# p128a.net
KiCad netlist of a schematic drawn in EAGLE
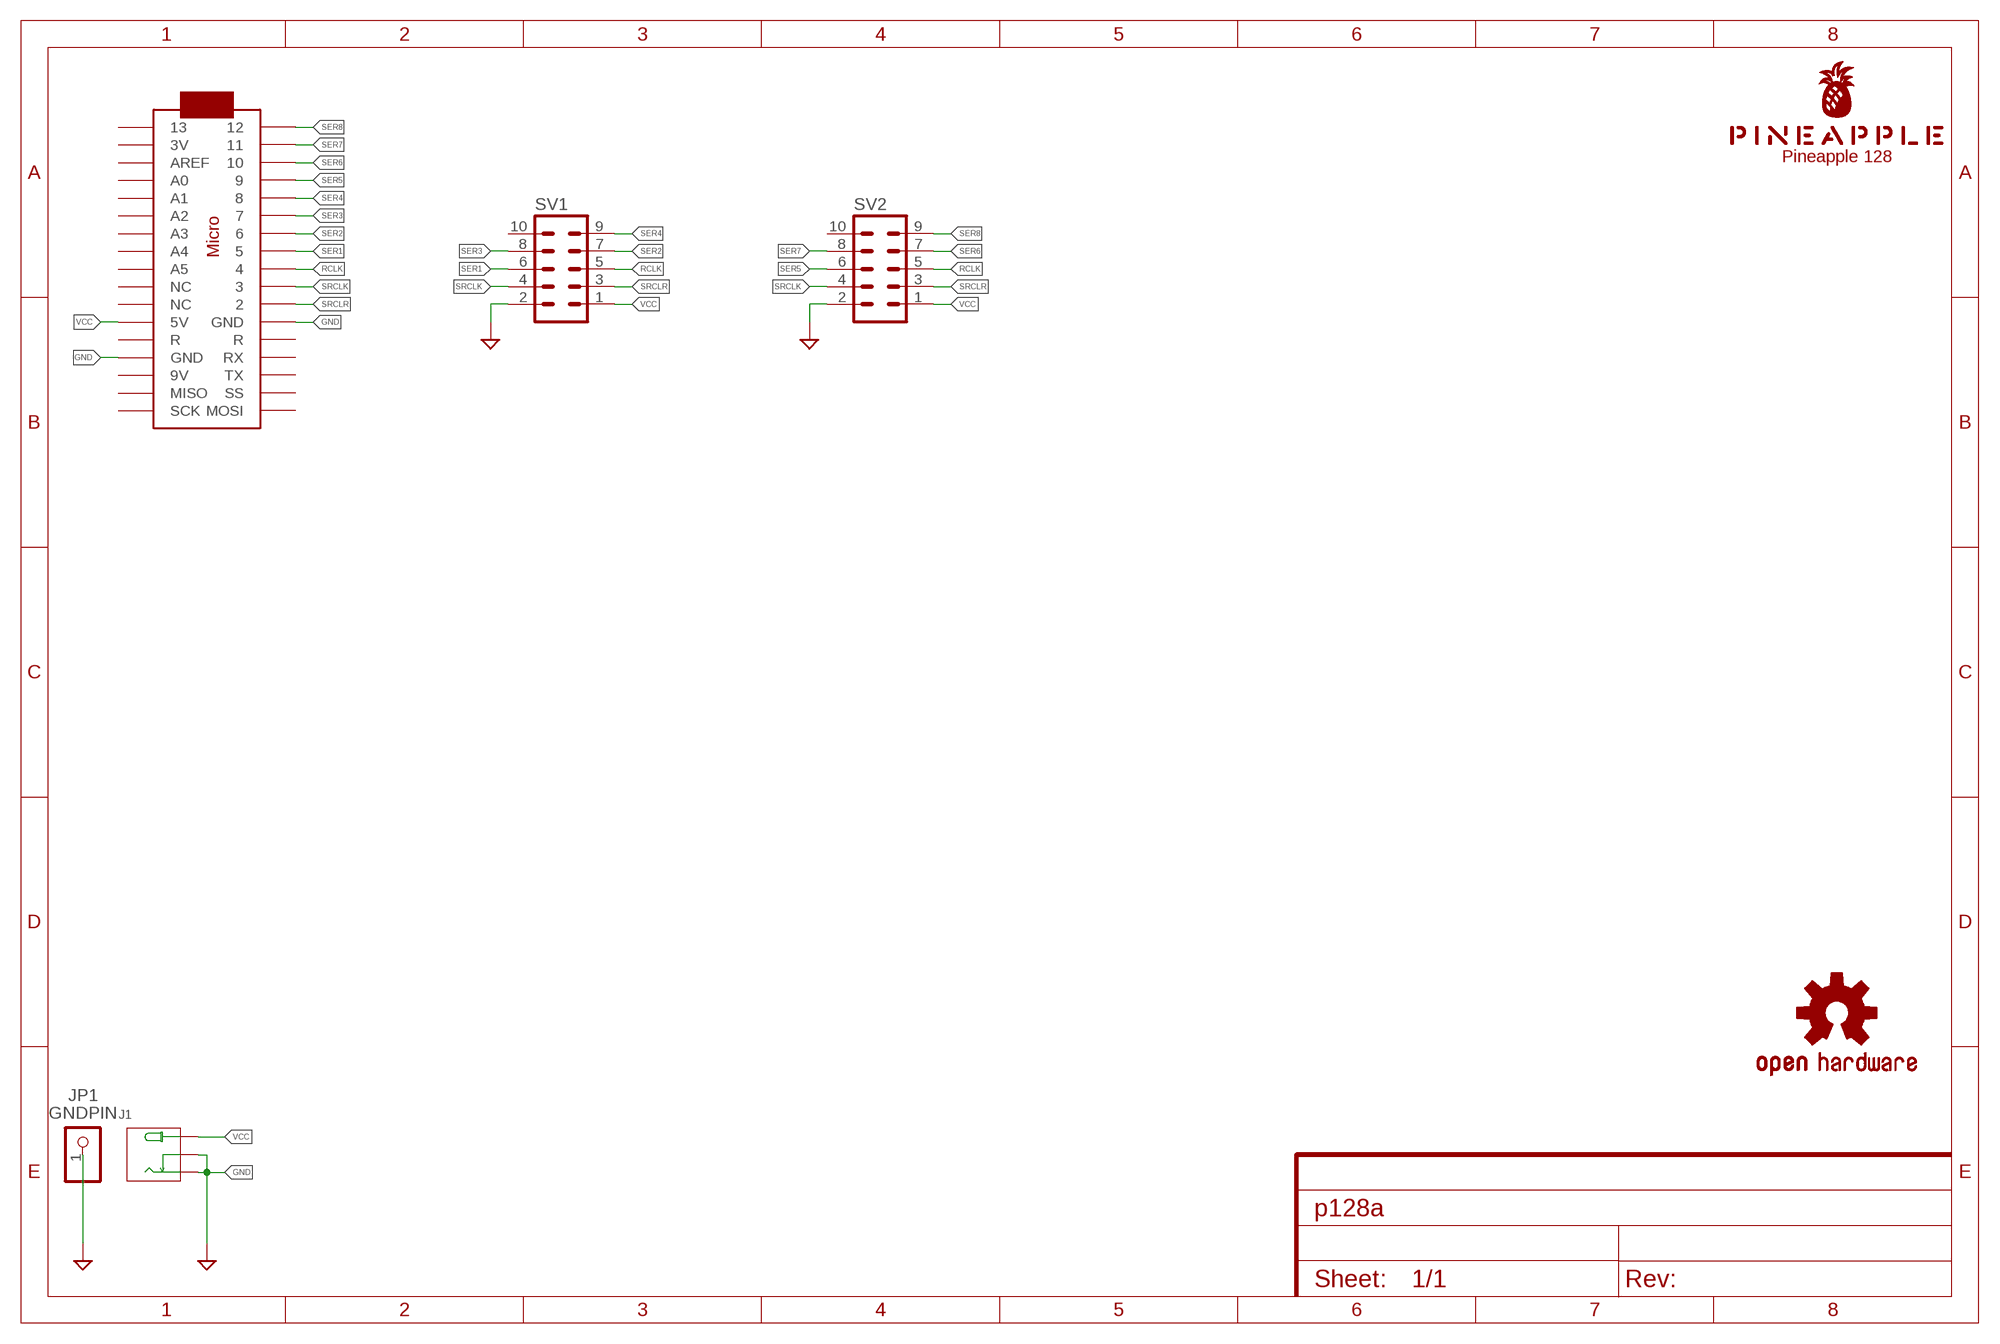
[diagram p0: schematic, sheet 1]

(export (version "E")
  (design (tool "Eeschema 10.0.6"))
  (components
    (comp (ref "J1")
      (value "JACK-DC-005'DC-005'")
      (footprint "eagle-import:3P-L14.2_W11.0_H9.0MM")
      (libsource (lib "eagle-import") (part "JACK-DC-005'DC-005'"))
    )
    (comp (ref "JP1")
      (value "GNDPIN")
      (footprint "eagle-import:1X01")
      (libsource (lib "eagle-import") (part "PINHD-1X1"))
    )
    (comp (ref "LOGO1")
      (value "OSHW-LOGOS-COPPER")
      (footprint "eagle-import:OSHW-LOGO-S_COPPER")
      (libsource (lib "eagle-import") (part "OSHW-LOGOS-COPPER"))
    )
    (comp (ref "MC1")
      (value "ARDUINOMICRO")
      (footprint "eagle-import:ARDUINOMICRO")
      (libsource (lib "eagle-import") (part "ARDUINOMICRO"))
    )
    (comp (ref "SV1")
      (value "ML10L")
      (footprint "eagle-import:ML10L")
      (libsource (lib "eagle-import") (part "ML10L"))
    )
    (comp (ref "SV2")
      (value "ML10L")
      (footprint "eagle-import:ML10L")
      (libsource (lib "eagle-import") (part "ML10L"))
    )
    (comp (ref "U$1")
      (value "PINEAPPLE450_SILK")
      (footprint "eagle-import:PINEAPPLE450_SILK")
      (libsource (lib "eagle-import") (part "PINEAPPLE450_SILK"))
    )
  )
  (nets
    (net (code "1") (name "GND") (class "Default")
      (node (ref "J1") (pin "-1") (pinfunction "-_-1") (pintype "bidirectional"))
      (node (ref "J1") (pin "-2") (pinfunction "CDN_-2") (pintype "bidirectional"))
      (node (ref "JP1") (pin "1") (pinfunction "1_1") (pintype "passive"))
      (node (ref "MC1") (pin "P$12") (pinfunction "GND_P$12") (pintype "bidirectional"))
      (node (ref "MC1") (pin "P$21") (pinfunction "GND_P$21") (pintype "bidirectional"))
      (node (ref "SV1") (pin "2") (pinfunction "2_2") (pintype "passive"))
      (node (ref "SV2") (pin "2") (pinfunction "2_2") (pintype "passive"))
    )
    (net (code "2") (name "RCLK") (class "Default")
      (node (ref "MC1") (pin "P$9") (pinfunction "4_P$9") (pintype "bidirectional"))
      (node (ref "SV1") (pin "5") (pinfunction "5_5") (pintype "passive"))
      (node (ref "SV2") (pin "5") (pinfunction "5_5") (pintype "passive"))
    )
    (net (code "3") (name "SER1") (class "Default")
      (node (ref "MC1") (pin "P$8") (pinfunction "5_P$8") (pintype "bidirectional"))
      (node (ref "SV1") (pin "6") (pinfunction "6_6") (pintype "passive"))
    )
    (net (code "4") (name "SER2") (class "Default")
      (node (ref "MC1") (pin "P$7") (pinfunction "6_P$7") (pintype "bidirectional"))
      (node (ref "SV1") (pin "7") (pinfunction "7_7") (pintype "passive"))
    )
    (net (code "5") (name "SER3") (class "Default")
      (node (ref "MC1") (pin "P$6") (pinfunction "7_P$6") (pintype "bidirectional"))
      (node (ref "SV1") (pin "8") (pinfunction "8_8") (pintype "passive"))
    )
    (net (code "6") (name "SER4") (class "Default")
      (node (ref "MC1") (pin "P$5") (pinfunction "8_P$5") (pintype "bidirectional"))
      (node (ref "SV1") (pin "9") (pinfunction "9_9") (pintype "passive"))
    )
    (net (code "7") (name "SER5") (class "Default")
      (node (ref "MC1") (pin "P$4") (pinfunction "9_P$4") (pintype "bidirectional"))
      (node (ref "SV2") (pin "6") (pinfunction "6_6") (pintype "passive"))
    )
    (net (code "8") (name "SER6") (class "Default")
      (node (ref "MC1") (pin "P$3") (pinfunction "10_P$3") (pintype "bidirectional"))
      (node (ref "SV2") (pin "7") (pinfunction "7_7") (pintype "passive"))
    )
    (net (code "9") (name "SER7") (class "Default")
      (node (ref "MC1") (pin "P$2") (pinfunction "11_P$2") (pintype "bidirectional"))
      (node (ref "SV2") (pin "8") (pinfunction "8_8") (pintype "passive"))
    )
    (net (code "10") (name "SER8") (class "Default")
      (node (ref "MC1") (pin "P$1") (pinfunction "12_P$1") (pintype "bidirectional"))
      (node (ref "SV2") (pin "9") (pinfunction "9_9") (pintype "passive"))
    )
    (net (code "11") (name "SRCLK") (class "Default")
      (node (ref "MC1") (pin "P$10") (pinfunction "3_P$10") (pintype "bidirectional"))
      (node (ref "SV1") (pin "4") (pinfunction "4_4") (pintype "passive"))
      (node (ref "SV2") (pin "4") (pinfunction "4_4") (pintype "passive"))
    )
    (net (code "12") (name "SRCLR") (class "Default")
      (node (ref "MC1") (pin "P$11") (pinfunction "2_P$11") (pintype "bidirectional"))
      (node (ref "SV1") (pin "3") (pinfunction "3_3") (pintype "passive"))
      (node (ref "SV2") (pin "3") (pinfunction "3_3") (pintype "passive"))
    )
    (net (code "13") (name "VCC") (class "Default")
      (node (ref "J1") (pin "+") (pinfunction "+_+") (pintype "bidirectional"))
      (node (ref "MC1") (pin "P$23") (pinfunction "5V_P$23") (pintype "bidirectional"))
      (node (ref "SV1") (pin "1") (pinfunction "1_1") (pintype "passive"))
      (node (ref "SV2") (pin "1") (pinfunction "1_1") (pintype "passive"))
    )
    (net (code "14") (name "unconnected-(MC1-3V-PadP$33)") (class "Default")
      (node (ref "MC1") (pin "P$33") (pinfunction "3V_P$33") (pintype "bidirectional"))
    )
    (net (code "15") (name "unconnected-(MC1-9V-PadP$20)") (class "Default")
      (node (ref "MC1") (pin "P$20") (pinfunction "9V_P$20") (pintype "bidirectional"))
    )
    (net (code "16") (name "unconnected-(MC1-13-PadP$34)") (class "Default")
      (node (ref "MC1") (pin "P$34") (pinfunction "13_P$34") (pintype "bidirectional"))
    )
    (net (code "17") (name "unconnected-(MC1-A0-PadP$31)") (class "Default")
      (node (ref "MC1") (pin "P$31") (pinfunction "A0_P$31") (pintype "bidirectional"))
    )
    (net (code "18") (name "unconnected-(MC1-A1-PadP$30)") (class "Default")
      (node (ref "MC1") (pin "P$30") (pinfunction "A1_P$30") (pintype "bidirectional"))
    )
    (net (code "19") (name "unconnected-(MC1-A2-PadP$29)") (class "Default")
      (node (ref "MC1") (pin "P$29") (pinfunction "A2_P$29") (pintype "bidirectional"))
    )
    (net (code "20") (name "unconnected-(MC1-A3-PadP$28)") (class "Default")
      (node (ref "MC1") (pin "P$28") (pinfunction "A3_P$28") (pintype "bidirectional"))
    )
    (net (code "21") (name "unconnected-(MC1-A4-PadP$27)") (class "Default")
      (node (ref "MC1") (pin "P$27") (pinfunction "A4_P$27") (pintype "bidirectional"))
    )
    (net (code "22") (name "unconnected-(MC1-A5-PadP$26)") (class "Default")
      (node (ref "MC1") (pin "P$26") (pinfunction "A5_P$26") (pintype "bidirectional"))
    )
    (net (code "23") (name "unconnected-(MC1-AREF-PadP$32)") (class "Default")
      (node (ref "MC1") (pin "P$32") (pinfunction "AREF_P$32") (pintype "bidirectional"))
    )
    (net (code "24") (name "unconnected-(MC1-MISO-PadP$19)") (class "Default")
      (node (ref "MC1") (pin "P$19") (pinfunction "MISO_P$19") (pintype "bidirectional"))
    )
    (net (code "25") (name "unconnected-(MC1-MOSI-PadP$17)") (class "Default")
      (node (ref "MC1") (pin "P$17") (pinfunction "MOSI_P$17") (pintype "bidirectional"))
    )
    (net (code "26") (name "unconnected-(MC1-NC-PadP$24)") (class "Default")
      (node (ref "MC1") (pin "P$24") (pinfunction "NC_P$24") (pintype "bidirectional"))
    )
    (net (code "27") (name "unconnected-(MC1-NC-PadP$25)") (class "Default")
      (node (ref "MC1") (pin "P$25") (pinfunction "NC_P$25") (pintype "bidirectional"))
    )
    (net (code "28") (name "unconnected-(MC1-R-PadP$13)") (class "Default")
      (node (ref "MC1") (pin "P$13") (pinfunction "R_P$13") (pintype "bidirectional"))
    )
    (net (code "29") (name "unconnected-(MC1-R-PadP$22)") (class "Default")
      (node (ref "MC1") (pin "P$22") (pinfunction "R_P$22") (pintype "bidirectional"))
    )
    (net (code "30") (name "unconnected-(MC1-RX-PadP$14)") (class "Default")
      (node (ref "MC1") (pin "P$14") (pinfunction "RX_P$14") (pintype "bidirectional"))
    )
    (net (code "31") (name "unconnected-(MC1-SCK-PadP$18)") (class "Default")
      (node (ref "MC1") (pin "P$18") (pinfunction "SCK_P$18") (pintype "bidirectional"))
    )
    (net (code "32") (name "unconnected-(MC1-SS-PadP$16)") (class "Default")
      (node (ref "MC1") (pin "P$16") (pinfunction "SS_P$16") (pintype "bidirectional"))
    )
    (net (code "33") (name "unconnected-(MC1-TX-PadP$15)") (class "Default")
      (node (ref "MC1") (pin "P$15") (pinfunction "TX_P$15") (pintype "bidirectional"))
    )
    (net (code "34") (name "unconnected-(SV1-Pad10)") (class "Default")
      (node (ref "SV1") (pin "10") (pinfunction "10_10") (pintype "passive"))
    )
    (net (code "35") (name "unconnected-(SV2-Pad10)") (class "Default")
      (node (ref "SV2") (pin "10") (pinfunction "10_10") (pintype "passive"))
    )
  )
)
